# SIMO_SWITCHER.net
KiCad netlist of a schematic drawn in Altium Designer
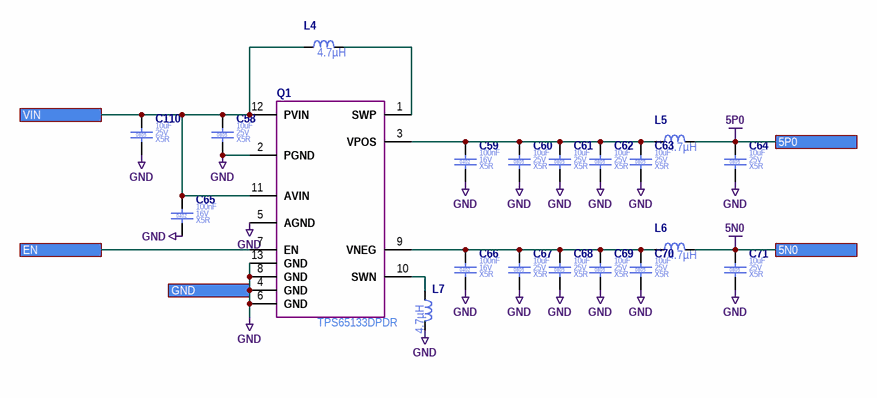
[diagram p0: SIMO_SWITCHER.SchDoc]

(export (version "E")
  (design (tool "Eeschema 10.0.6"))
  (components
    (comp (ref "C58")
      (value "C_10UF_25V_X5R_0805_10")
      (footprint "C_0805_2012")
      (description "Ceramic Capacitor")
      (fields
        (field (name "CASE/PACKAGE") "0805")
        (field (name "VOLTAGE RATING (DC)") "25V")
        (field (name "DIELECTRIC") "X5R")
        (field (name "CAPACITANCE") "10uF")
        (field (name "TOLERANCE") "10%")
        (field (name "MANUFACTURER PART NUMBER") "CL21A106KAYNNNE")
      )
      (libsource (lib "7Sigma") (part "C"))
    )
    (comp (ref "C59")
      (value "C_100NF_16V_X5R_0402_10")
      (footprint "C_0402_1005")
      (description "Ceramic Capacitor")
      (fields
        (field (name "CASE/PACKAGE") "0402")
        (field (name "VOLTAGE RATING (DC)") "16V")
        (field (name "DIELECTRIC") "X5R")
        (field (name "CAPACITANCE") "100nF")
        (field (name "TOLERANCE") "10%")
        (field (name "MANUFACTURER PART NUMBER") "EMK105BJ104KV-F")
      )
      (libsource (lib "7Sigma") (part "C"))
    )
    (comp (ref "C60")
      (value "C_10UF_25V_X5R_0805_10")
      (footprint "C_0805_2012")
      (description "Ceramic Capacitor")
      (fields
        (field (name "CASE/PACKAGE") "0805")
        (field (name "VOLTAGE RATING (DC)") "25V")
        (field (name "DIELECTRIC") "X5R")
        (field (name "CAPACITANCE") "10uF")
        (field (name "TOLERANCE") "10%")
        (field (name "MANUFACTURER PART NUMBER") "CL21A106KAYNNNE")
      )
      (libsource (lib "7Sigma") (part "C"))
    )
    (comp (ref "C61")
      (value "C_10UF_25V_X5R_0805_10")
      (footprint "C_0805_2012")
      (description "Ceramic Capacitor")
      (fields
        (field (name "CASE/PACKAGE") "0805")
        (field (name "VOLTAGE RATING (DC)") "25V")
        (field (name "DIELECTRIC") "X5R")
        (field (name "CAPACITANCE") "10uF")
        (field (name "TOLERANCE") "10%")
        (field (name "MANUFACTURER PART NUMBER") "CL21A106KAYNNNE")
      )
      (libsource (lib "7Sigma") (part "C"))
    )
    (comp (ref "C62")
      (value "C_10UF_25V_X5R_0805_10")
      (footprint "C_0805_2012")
      (description "Ceramic Capacitor")
      (fields
        (field (name "CASE/PACKAGE") "0805")
        (field (name "VOLTAGE RATING (DC)") "25V")
        (field (name "DIELECTRIC") "X5R")
        (field (name "CAPACITANCE") "10uF")
        (field (name "TOLERANCE") "10%")
        (field (name "MANUFACTURER PART NUMBER") "CL21A106KAYNNNE")
      )
      (libsource (lib "7Sigma") (part "C"))
    )
    (comp (ref "C63")
      (value "C_10UF_25V_X5R_0805_10")
      (footprint "C_0805_2012")
      (description "Ceramic Capacitor")
      (fields
        (field (name "CASE/PACKAGE") "0805")
        (field (name "VOLTAGE RATING (DC)") "25V")
        (field (name "DIELECTRIC") "X5R")
        (field (name "CAPACITANCE") "10uF")
        (field (name "TOLERANCE") "10%")
        (field (name "MANUFACTURER PART NUMBER") "CL21A106KAYNNNE")
      )
      (libsource (lib "7Sigma") (part "C"))
    )
    (comp (ref "C64")
      (value "C_10UF_25V_X5R_0805_10")
      (footprint "C_0805_2012")
      (description "Ceramic Capacitor")
      (fields
        (field (name "CASE/PACKAGE") "0805")
        (field (name "VOLTAGE RATING (DC)") "25V")
        (field (name "DIELECTRIC") "X5R")
        (field (name "CAPACITANCE") "10uF")
        (field (name "TOLERANCE") "10%")
        (field (name "MANUFACTURER PART NUMBER") "CL21A106KAYNNNE")
      )
      (libsource (lib "7Sigma") (part "C"))
    )
    (comp (ref "C65")
      (value "C_100NF_16V_X5R_0402_10")
      (footprint "C_0402_1005")
      (description "Ceramic Capacitor")
      (fields
        (field (name "CASE/PACKAGE") "0402")
        (field (name "VOLTAGE RATING (DC)") "16V")
        (field (name "DIELECTRIC") "X5R")
        (field (name "CAPACITANCE") "100nF")
        (field (name "TOLERANCE") "10%")
        (field (name "MANUFACTURER PART NUMBER") "EMK105BJ104KV-F")
      )
      (libsource (lib "7Sigma") (part "C"))
    )
    (comp (ref "C66")
      (value "C_100NF_16V_X5R_0402_10")
      (footprint "C_0402_1005")
      (description "Ceramic Capacitor")
      (fields
        (field (name "CASE/PACKAGE") "0402")
        (field (name "VOLTAGE RATING (DC)") "16V")
        (field (name "DIELECTRIC") "X5R")
        (field (name "CAPACITANCE") "100nF")
        (field (name "TOLERANCE") "10%")
        (field (name "MANUFACTURER PART NUMBER") "EMK105BJ104KV-F")
      )
      (libsource (lib "7Sigma") (part "C"))
    )
    (comp (ref "C67")
      (value "C_10UF_25V_X5R_0805_10")
      (footprint "C_0805_2012")
      (description "Ceramic Capacitor")
      (fields
        (field (name "CASE/PACKAGE") "0805")
        (field (name "VOLTAGE RATING (DC)") "25V")
        (field (name "DIELECTRIC") "X5R")
        (field (name "CAPACITANCE") "10uF")
        (field (name "TOLERANCE") "10%")
        (field (name "MANUFACTURER PART NUMBER") "CL21A106KAYNNNE")
      )
      (libsource (lib "7Sigma") (part "C"))
    )
    (comp (ref "C68")
      (value "C_10UF_25V_X5R_0805_10")
      (footprint "C_0805_2012")
      (description "Ceramic Capacitor")
      (fields
        (field (name "CASE/PACKAGE") "0805")
        (field (name "VOLTAGE RATING (DC)") "25V")
        (field (name "DIELECTRIC") "X5R")
        (field (name "CAPACITANCE") "10uF")
        (field (name "TOLERANCE") "10%")
        (field (name "MANUFACTURER PART NUMBER") "CL21A106KAYNNNE")
      )
      (libsource (lib "7Sigma") (part "C"))
    )
    (comp (ref "C69")
      (value "C_10UF_25V_X5R_0805_10")
      (footprint "C_0805_2012")
      (description "Ceramic Capacitor")
      (fields
        (field (name "CASE/PACKAGE") "0805")
        (field (name "VOLTAGE RATING (DC)") "25V")
        (field (name "DIELECTRIC") "X5R")
        (field (name "CAPACITANCE") "10uF")
        (field (name "TOLERANCE") "10%")
        (field (name "MANUFACTURER PART NUMBER") "CL21A106KAYNNNE")
      )
      (libsource (lib "7Sigma") (part "C"))
    )
    (comp (ref "C70")
      (value "C_10UF_25V_X5R_0805_10")
      (footprint "C_0805_2012")
      (description "Ceramic Capacitor")
      (fields
        (field (name "CASE/PACKAGE") "0805")
        (field (name "VOLTAGE RATING (DC)") "25V")
        (field (name "DIELECTRIC") "X5R")
        (field (name "CAPACITANCE") "10uF")
        (field (name "TOLERANCE") "10%")
        (field (name "MANUFACTURER PART NUMBER") "CL21A106KAYNNNE")
      )
      (libsource (lib "7Sigma") (part "C"))
    )
    (comp (ref "C71")
      (value "C_10UF_25V_X5R_0805_10")
      (footprint "C_0805_2012")
      (description "Ceramic Capacitor")
      (fields
        (field (name "CASE/PACKAGE") "0805")
        (field (name "VOLTAGE RATING (DC)") "25V")
        (field (name "DIELECTRIC") "X5R")
        (field (name "CAPACITANCE") "10uF")
        (field (name "TOLERANCE") "10%")
        (field (name "MANUFACTURER PART NUMBER") "CL21A106KAYNNNE")
      )
      (libsource (lib "7Sigma") (part "C"))
    )
    (comp (ref "C110")
      (value "C_10UF_25V_X5R_0805_10")
      (footprint "C_0805_2012")
      (description "Ceramic Capacitor")
      (fields
        (field (name "CASE/PACKAGE") "0805")
        (field (name "VOLTAGE RATING (DC)") "25V")
        (field (name "DIELECTRIC") "X5R")
        (field (name "CAPACITANCE") "10uF")
        (field (name "TOLERANCE") "10%")
        (field (name "MANUFACTURER PART NUMBER") "CL21A106KAYNNNE")
      )
      (libsource (lib "7Sigma") (part "C"))
    )
    (comp (ref "L4")
      (value "1239AS-H-4R7M=P2")
      (footprint "L_1008_2520")
      (description "Power Inductor")
      (fields
        (field (name "INDUCTANCE") "4.7µH")
        (field (name "MANUFACTURER") "Murata Electronics")
        (field (name "TOLERANCE") "20%")
      )
      (libsource (lib "7Sigma") (part "L"))
    )
    (comp (ref "L5")
      (value "1239AS-H-4R7M=P2")
      (footprint "L_1008_2520")
      (description "Power Inductor")
      (fields
        (field (name "INDUCTANCE") "4.7µH")
        (field (name "MANUFACTURER") "Murata Electronics")
        (field (name "TOLERANCE") "20%")
      )
      (libsource (lib "7Sigma") (part "L"))
    )
    (comp (ref "L6")
      (value "1239AS-H-4R7M=P2")
      (footprint "L_1008_2520")
      (description "Power Inductor")
      (fields
        (field (name "INDUCTANCE") "4.7µH")
        (field (name "MANUFACTURER") "Murata Electronics")
        (field (name "TOLERANCE") "20%")
      )
      (libsource (lib "7Sigma") (part "L"))
    )
    (comp (ref "L7")
      (value "1239AS-H-4R7M=P2")
      (footprint "L_1008_2520")
      (description "Power Inductor")
      (fields
        (field (name "INDUCTANCE") "4.7µH")
        (field (name "MANUFACTURER") "Murata Electronics")
        (field (name "TOLERANCE") "20%")
      )
      (libsource (lib "") (part "L_1"))
    )
    (comp (ref "Q1")
      (value "TPS65133DPDR")
      (footprint "SON45P300X80_HS-13N")
      (description "Split-Rail Converter, ±5V, 250mA Dual Output Power Supply")
      (fields
        (field (name "MANUFACTURER PART NUMBER") "TPS65133DPDR")
        (field (name "MANUFACTURER") "Texas Instruments")
      )
      (libsource (lib "7Sigma") (part "TPS65133DPDR"))
    )
  )
  (nets
    (net (code "1") (name "/EN") (class "Default")
      (node (ref "Q1") (pin "7") (pinfunction "EN_7") (pintype "passive"))
    )
    (net (code "2") (name "/VIN") (class "Default")
      (node (ref "C110") (pin "1") (pinfunction "1_1") (pintype "passive"))
      (node (ref "C58") (pin "1") (pinfunction "1_1") (pintype "passive"))
      (node (ref "C65") (pin "1") (pinfunction "1_1") (pintype "passive"))
      (node (ref "L4") (pin "1") (pinfunction "1_1") (pintype "passive"))
      (node (ref "Q1") (pin "11") (pinfunction "AVIN_11") (pintype "passive"))
      (node (ref "Q1") (pin "12") (pinfunction "PVIN_12") (pintype "passive"))
    )
    (net (code "3") (name "5N0") (class "Default")
      (node (ref "C71") (pin "1") (pinfunction "1_1") (pintype "passive"))
      (node (ref "L6") (pin "2") (pinfunction "2_2") (pintype "passive"))
    )
    (net (code "4") (name "5P0") (class "Default")
      (node (ref "C64") (pin "1") (pinfunction "1_1") (pintype "passive"))
      (node (ref "L5") (pin "2") (pinfunction "2_2") (pintype "passive"))
    )
    (net (code "5") (name "GND") (class "Default")
      (node (ref "C110") (pin "2") (pinfunction "2_2") (pintype "passive"))
      (node (ref "C58") (pin "2") (pinfunction "2_2") (pintype "passive"))
      (node (ref "C59") (pin "2") (pinfunction "2_2") (pintype "passive"))
      (node (ref "C60") (pin "2") (pinfunction "2_2") (pintype "passive"))
      (node (ref "C61") (pin "2") (pinfunction "2_2") (pintype "passive"))
      (node (ref "C62") (pin "2") (pinfunction "2_2") (pintype "passive"))
      (node (ref "C63") (pin "2") (pinfunction "2_2") (pintype "passive"))
      (node (ref "C64") (pin "2") (pinfunction "2_2") (pintype "passive"))
      (node (ref "C65") (pin "2") (pinfunction "2_2") (pintype "passive"))
      (node (ref "C66") (pin "2") (pinfunction "2_2") (pintype "passive"))
      (node (ref "C67") (pin "2") (pinfunction "2_2") (pintype "passive"))
      (node (ref "C68") (pin "2") (pinfunction "2_2") (pintype "passive"))
      (node (ref "C69") (pin "2") (pinfunction "2_2") (pintype "passive"))
      (node (ref "C70") (pin "2") (pinfunction "2_2") (pintype "passive"))
      (node (ref "C71") (pin "2") (pinfunction "2_2") (pintype "passive"))
      (node (ref "L7") (pin "2") (pinfunction "2_2") (pintype "passive"))
      (node (ref "Q1") (pin "13") (pinfunction "GND_13") (pintype "passive"))
      (node (ref "Q1") (pin "2") (pinfunction "PGND_2") (pintype "passive"))
      (node (ref "Q1") (pin "4") (pinfunction "GND_4") (pintype "passive"))
      (node (ref "Q1") (pin "5") (pinfunction "AGND_5") (pintype "passive"))
      (node (ref "Q1") (pin "6") (pinfunction "GND_6") (pintype "passive"))
      (node (ref "Q1") (pin "8") (pinfunction "GND_8") (pintype "passive"))
    )
    (net (code "6") (name "Net-(Q1-SWN)") (class "Default")
      (node (ref "L7") (pin "1") (pinfunction "1_1") (pintype "passive"))
      (node (ref "Q1") (pin "10") (pinfunction "SWN_10") (pintype "passive"))
    )
    (net (code "7") (name "Net-(Q1-SWP)") (class "Default")
      (node (ref "L4") (pin "2") (pinfunction "2_2") (pintype "passive"))
      (node (ref "Q1") (pin "1") (pinfunction "SWP_1") (pintype "passive"))
    )
    (net (code "8") (name "Net-(Q1-VNEG)") (class "Default")
      (node (ref "C66") (pin "1") (pinfunction "1_1") (pintype "passive"))
      (node (ref "C67") (pin "1") (pinfunction "1_1") (pintype "passive"))
      (node (ref "C68") (pin "1") (pinfunction "1_1") (pintype "passive"))
      (node (ref "C69") (pin "1") (pinfunction "1_1") (pintype "passive"))
      (node (ref "C70") (pin "1") (pinfunction "1_1") (pintype "passive"))
      (node (ref "L6") (pin "1") (pinfunction "1_1") (pintype "passive"))
      (node (ref "Q1") (pin "9") (pinfunction "VNEG_9") (pintype "passive"))
    )
    (net (code "9") (name "Net-(Q1-VPOS)") (class "Default")
      (node (ref "C59") (pin "1") (pinfunction "1_1") (pintype "passive"))
      (node (ref "C60") (pin "1") (pinfunction "1_1") (pintype "passive"))
      (node (ref "C61") (pin "1") (pinfunction "1_1") (pintype "passive"))
      (node (ref "C62") (pin "1") (pinfunction "1_1") (pintype "passive"))
      (node (ref "C63") (pin "1") (pinfunction "1_1") (pintype "passive"))
      (node (ref "L5") (pin "1") (pinfunction "1_1") (pintype "passive"))
      (node (ref "Q1") (pin "3") (pinfunction "VPOS_3") (pintype "passive"))
    )
  )
)
